# ReboostV2_MC.net
KiCad netlist of a schematic drawn in Altium Designer
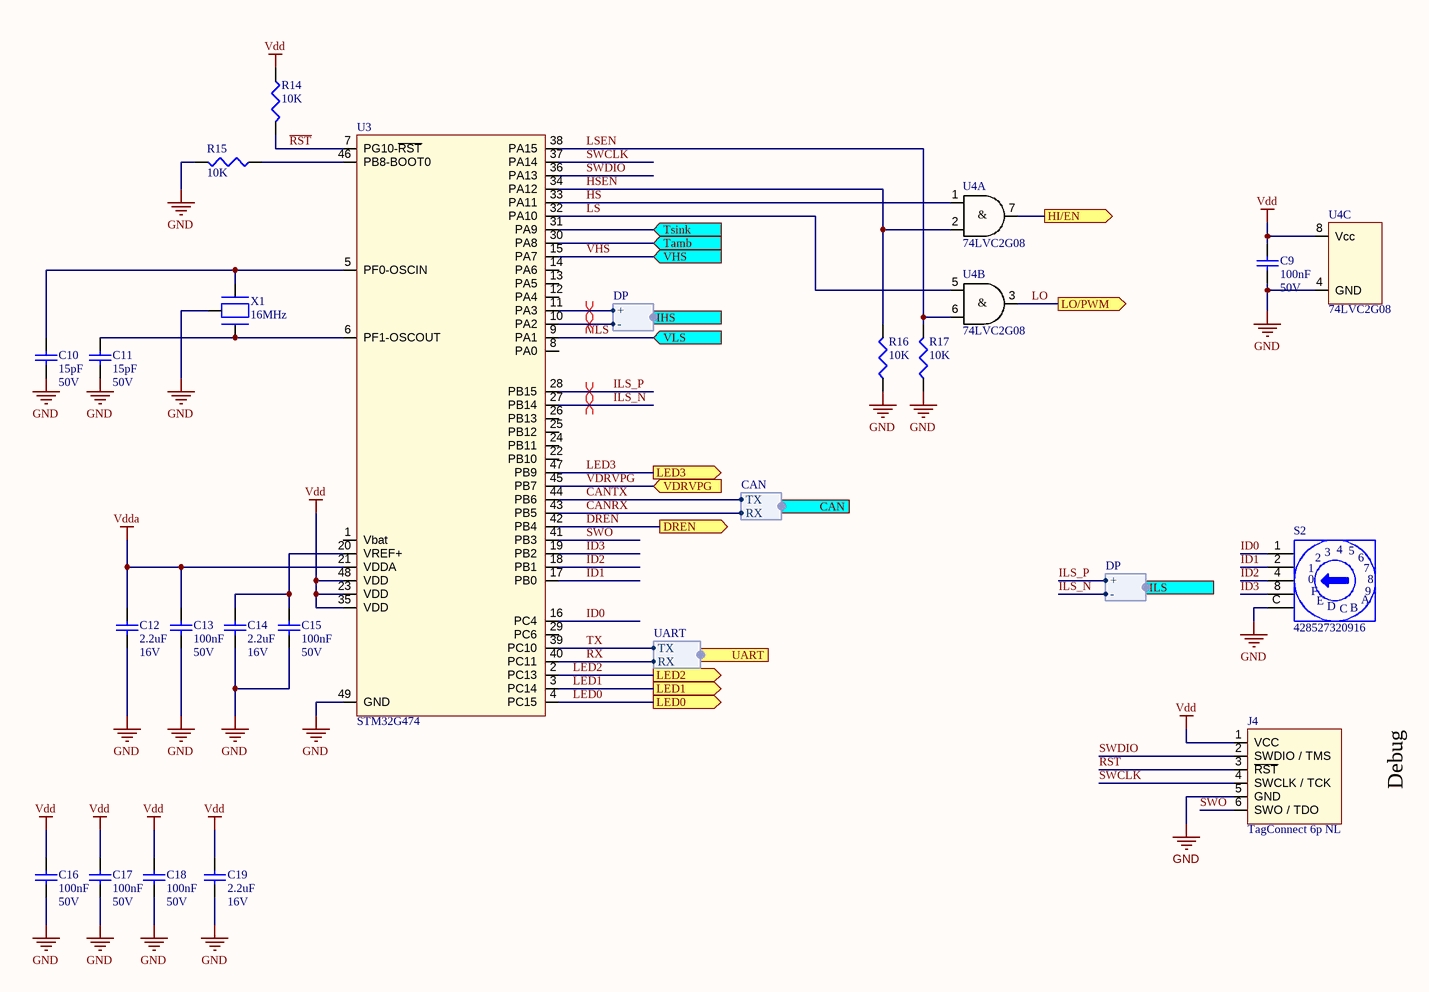
[diagram p0: ReboostV2_MC.SchDoc]

(export (version "E")
  (design (tool "Eeschema 10.0.6"))
  (components
    (comp (ref "C9")
      (value "100nF")
      (footprint "C0603")
      (description "Capacitor, 100nF, 50V, X7R")
      (fields
        (field (name "VOLTAGE RATING") "50V")
        (field (name "MANUFACTURER") "MULTICOMP")
        (field (name "MANUFACTURER PART NUMBER") "MCCA000255")
      )
      (libsource (lib "Reboostv2") (part "100nF/0603/CER/50V"))
    )
    (comp (ref "C10")
      (value "15pF")
      (footprint "C0603")
      (description "Capacitor, 15pF, 50V, C0G / NP0")
      (fields
        (field (name "VOLTAGE RATING") "50V")
        (field (name "MANUFACTURER") "MULTICOMP")
        (field (name "MANUFACTURER PART NUMBER") "MCCA000194")
      )
      (libsource (lib "Reboostv2") (part "15pF/0603/CER/50V"))
    )
    (comp (ref "C11")
      (value "15pF")
      (footprint "C0603")
      (description "Capacitor, 15pF, 50V, C0G / NP0")
      (fields
        (field (name "VOLTAGE RATING") "50V")
        (field (name "MANUFACTURER") "MULTICOMP")
        (field (name "MANUFACTURER PART NUMBER") "MCCA000194")
      )
      (libsource (lib "Reboostv2") (part "15pF/0603/CER/50V"))
    )
    (comp (ref "C12")
      (value "2.2uF")
      (footprint "C0603")
      (description "Capacitor, 2.2uF, 16V, X5R")
      (fields
        (field (name "VOLTAGE RATING") "16V")
        (field (name "MANUFACTURER") "MURATA")
        (field (name "MANUFACTURER PART NUMBER") "GRM188R61C225KE15D")
      )
      (libsource (lib "Reboostv2") (part "2.2uF/0603/CER/16V"))
    )
    (comp (ref "C13")
      (value "100nF")
      (footprint "C0603")
      (description "Capacitor, 100nF, 50V, X7R")
      (fields
        (field (name "VOLTAGE RATING") "50V")
        (field (name "MANUFACTURER") "MULTICOMP")
        (field (name "MANUFACTURER PART NUMBER") "MCCA000255")
      )
      (libsource (lib "Reboostv2") (part "100nF/0603/CER/50V"))
    )
    (comp (ref "C14")
      (value "2.2uF")
      (footprint "C0603")
      (description "Capacitor, 2.2uF, 16V, X5R")
      (fields
        (field (name "VOLTAGE RATING") "16V")
        (field (name "MANUFACTURER") "MURATA")
        (field (name "MANUFACTURER PART NUMBER") "GRM188R61C225KE15D")
      )
      (libsource (lib "Reboostv2") (part "2.2uF/0603/CER/16V"))
    )
    (comp (ref "C15")
      (value "100nF")
      (footprint "C0603")
      (description "Capacitor, 100nF, 50V, X7R")
      (fields
        (field (name "VOLTAGE RATING") "50V")
        (field (name "MANUFACTURER") "MULTICOMP")
        (field (name "MANUFACTURER PART NUMBER") "MCCA000255")
      )
      (libsource (lib "Reboostv2") (part "100nF/0603/CER/50V"))
    )
    (comp (ref "C16")
      (value "100nF")
      (footprint "C0603")
      (description "Capacitor, 100nF, 50V, X7R")
      (fields
        (field (name "VOLTAGE RATING") "50V")
        (field (name "MANUFACTURER") "MULTICOMP")
        (field (name "MANUFACTURER PART NUMBER") "MCCA000255")
      )
      (libsource (lib "Reboostv2") (part "100nF/0603/CER/50V"))
    )
    (comp (ref "C17")
      (value "100nF")
      (footprint "C0603")
      (description "Capacitor, 100nF, 50V, X7R")
      (fields
        (field (name "VOLTAGE RATING") "50V")
        (field (name "MANUFACTURER") "MULTICOMP")
        (field (name "MANUFACTURER PART NUMBER") "MCCA000255")
      )
      (libsource (lib "Reboostv2") (part "100nF/0603/CER/50V"))
    )
    (comp (ref "C18")
      (value "100nF")
      (footprint "C0603")
      (description "Capacitor, 100nF, 50V, X7R")
      (fields
        (field (name "VOLTAGE RATING") "50V")
        (field (name "MANUFACTURER") "MULTICOMP")
        (field (name "MANUFACTURER PART NUMBER") "MCCA000255")
      )
      (libsource (lib "Reboostv2") (part "100nF/0603/CER/50V"))
    )
    (comp (ref "C19")
      (value "2.2uF")
      (footprint "C0603")
      (description "Capacitor, 2.2uF, 16V, X5R")
      (fields
        (field (name "VOLTAGE RATING") "16V")
        (field (name "MANUFACTURER") "MURATA")
        (field (name "MANUFACTURER PART NUMBER") "GRM188R61C225KE15D")
      )
      (libsource (lib "Reboostv2") (part "2.2uF/0603/CER/16V"))
    )
    (comp (ref "J4")
      (value "TagConnect 6p NL")
      (footprint "TC2030-IDC-NL")
      (description "“No Legs” 6-pin Plug-of-Nails™ Cable fitted with a 6-pin 0.1″ pitch ribbon connector.")
      (fields
        (field (name "MANUFACTURER") "Tag-Connect LLC")
        (field (name "MANUFACTURER PART NUMBER") "TC2030-IDC-ND")
      )
      (libsource (lib "Reboostv2") (part "TC2030-IDC"))
    )
    (comp (ref "R14")
      (value "10K")
      (footprint "0603")
      (description "Resistor, 10K, 1%, 0.063W, 50V, 100PPM, 0603")
      (fields
        (field (name "MANUFACTURER") "VISHAY DRALORIC")
        (field (name "MANUFACTURER PART NUMBER") "CRCW060310K0FKEA")
      )
      (libsource (lib "Reboostv2") (part "10K/0603/0063W/50V"))
    )
    (comp (ref "R15")
      (value "10K")
      (footprint "0603")
      (description "Resistor, 10K, 1%, 0.063W, 50V, 100PPM, 0603")
      (fields
        (field (name "MANUFACTURER") "VISHAY DRALORIC")
        (field (name "MANUFACTURER PART NUMBER") "CRCW060310K0FKEA")
      )
      (libsource (lib "Reboostv2") (part "10K/0603/0063W/50V"))
    )
    (comp (ref "R16")
      (value "10K")
      (footprint "0603")
      (description "Resistor, 10K, 1%, 0.063W, 50V, 100PPM, 0603")
      (fields
        (field (name "MANUFACTURER") "VISHAY DRALORIC")
        (field (name "MANUFACTURER PART NUMBER") "CRCW060310K0FKEA")
      )
      (libsource (lib "Reboostv2") (part "10K/0603/0063W/50V"))
    )
    (comp (ref "R17")
      (value "10K")
      (footprint "0603")
      (description "Resistor, 10K, 1%, 0.063W, 50V, 100PPM, 0603")
      (fields
        (field (name "MANUFACTURER") "VISHAY DRALORIC")
        (field (name "MANUFACTURER PART NUMBER") "CRCW060310K0FKEA")
      )
      (libsource (lib "Reboostv2") (part "10K/0603/0063W/50V"))
    )
    (comp (ref "S2")
      (value "428527320916")
      (footprint "42852732091x_16p")
      (description "WS-ROTV THT Rotary Switch with Arrow Type Actuator, 10x10mm, 16 positions")
      (fields (field (name "MANUFACTURER") "Wurth Elektronik") (field (name "PUBLISHER") "Wurth Elektronik"))
      (libsource (lib "Reboostv2") (part "428527320916"))
    )
    (comp (ref "U3")
      (value "STM32G474")
      (footprint "QFN48")
      (description "ARM MCU, STM32 Family STM32G4 Series Microcontrollers, ARM Cortex-M4F, 32bit, 170 MHz, 512 KB")
      (fields (field (name "MANUFACTURER") "STMicroelectronics") (field (name "MPN") "STM32G474CEU6"))
      (libsource (lib "Reboostv2") (part "STM32G474CEU6"))
    )
    (comp (ref "U4")
      (value "74LVC2G08")
      (footprint "TSSOP8")
      (description "Dual 2-input AND gate")
      (fields
        (field (name "MANUFACTURER") "Nexperia")
        (field (name "MANUFACTURER PART NUMBER") "74LVC2G08DP,125")
      )
      (libsource (lib "Reboostv2") (part "74LVC2G08"))
    )
    (comp (ref "X1")
      (value "16MHz")
      (footprint "7M")
      (description "CRYSTAL, 16MHz,18PF CL, 3.2X2.5MM SMT")
      (fields (field (name "MANUFACTURER") "TXC") (field (name "MANUFACTURER PART NUMBER") "7M-16.000MAAJ-T"))
      (libsource (lib "Reboostv2") (part "7M-16.000MAAJ-T"))
    )
  )
  (nets
    (net (code "4") (name "/CANRX") (class "Default")
      (node (ref "U3") (pin "43") (pinfunction "PB5_43") (pintype "passive"))
    )
    (net (code "5") (name "/CANTX") (class "Default")
      (node (ref "U3") (pin "44") (pinfunction "PB6_44") (pintype "passive"))
    )
    (net (code "6") (name "/DREN") (class "Default")
      (node (ref "U3") (pin "42") (pinfunction "PB4_42") (pintype "passive"))
    )
    (net (code "7") (name "/HI{slash}EN") (class "Default")
      (node (ref "U4") (pin "7") (pinfunction "Y_7") (pintype "passive"))
    )
    (net (code "8") (name "/HS") (class "Default")
      (node (ref "U3") (pin "33") (pinfunction "PA11_33") (pintype "passive"))
      (node (ref "U4") (pin "1") (pinfunction "A_1") (pintype "passive"))
    )
    (net (code "9") (name "/HSEN") (class "Default")
      (node (ref "R16") (pin "2") (pinfunction "2_2") (pintype "passive"))
      (node (ref "U3") (pin "34") (pinfunction "PA12_34") (pintype "passive"))
      (node (ref "U4") (pin "2") (pinfunction "B_2") (pintype "passive"))
    )
    (net (code "10") (name "/ID0") (class "Default")
      (node (ref "S2") (pin "1") (pinfunction "1_1") (pintype "passive"))
      (node (ref "U3") (pin "16") (pinfunction "PC4_16") (pintype "passive"))
    )
    (net (code "11") (name "/ID1") (class "Default")
      (node (ref "S2") (pin "2") (pinfunction "2_2") (pintype "passive"))
      (node (ref "U3") (pin "17") (pinfunction "PB0_17") (pintype "passive"))
    )
    (net (code "12") (name "/ID2") (class "Default")
      (node (ref "S2") (pin "4") (pinfunction "4_4") (pintype "passive"))
      (node (ref "U3") (pin "18") (pinfunction "PB1_18") (pintype "passive"))
    )
    (net (code "13") (name "/ID3") (class "Default")
      (node (ref "S2") (pin "8") (pinfunction "8_8") (pintype "passive"))
      (node (ref "U3") (pin "19") (pinfunction "PB2_19") (pintype "passive"))
    )
    (net (code "14") (name "/ILS_N") (class "Default")
      (node (ref "U3") (pin "27") (pinfunction "PB14_27") (pintype "passive"))
    )
    (net (code "15") (name "/ILS_P") (class "Default")
      (node (ref "U3") (pin "28") (pinfunction "PB15_28") (pintype "passive"))
    )
    (net (code "16") (name "/LED0") (class "Default")
      (node (ref "U3") (pin "4") (pinfunction "PC15_4") (pintype "passive"))
    )
    (net (code "17") (name "/LED1") (class "Default")
      (node (ref "U3") (pin "3") (pinfunction "PC14_3") (pintype "passive"))
    )
    (net (code "18") (name "/LED2") (class "Default")
      (node (ref "U3") (pin "2") (pinfunction "PC13_2") (pintype "passive"))
    )
    (net (code "19") (name "/LED3") (class "Default")
      (node (ref "U3") (pin "47") (pinfunction "PB9_47") (pintype "passive"))
    )
    (net (code "20") (name "/LO") (class "Default")
      (node (ref "U4") (pin "3") (pinfunction "Y_3") (pintype "passive"))
    )
    (net (code "21") (name "/LS") (class "Default")
      (node (ref "U3") (pin "32") (pinfunction "PA10_32") (pintype "passive"))
      (node (ref "U4") (pin "5") (pinfunction "A_5") (pintype "passive"))
    )
    (net (code "22") (name "/LSEN") (class "Default")
      (node (ref "R17") (pin "2") (pinfunction "2_2") (pintype "passive"))
      (node (ref "U3") (pin "38") (pinfunction "PA15_38") (pintype "passive"))
      (node (ref "U4") (pin "6") (pinfunction "B_6") (pintype "passive"))
    )
    (net (code "23") (name "/RX") (class "Default")
      (node (ref "U3") (pin "40") (pinfunction "PC11_40") (pintype "passive"))
    )
    (net (code "24") (name "/SWCLK") (class "Default")
      (node (ref "J4") (pin "4") (pinfunction "SWCLK_/_TCK_4") (pintype "passive"))
      (node (ref "U3") (pin "37") (pinfunction "PA14_37") (pintype "passive"))
    )
    (net (code "25") (name "/SWDIO") (class "Default")
      (node (ref "J4") (pin "2") (pinfunction "SWDIO_/_TMS_2") (pintype "passive"))
      (node (ref "U3") (pin "36") (pinfunction "PA13_36") (pintype "passive"))
    )
    (net (code "26") (name "/SWO") (class "Default")
      (node (ref "J4") (pin "6") (pinfunction "SWO_/_TDO_6") (pintype "passive"))
      (node (ref "U3") (pin "41") (pinfunction "PB3_41") (pintype "passive"))
    )
    (net (code "27") (name "/TX") (class "Default")
      (node (ref "U3") (pin "39") (pinfunction "PC10_39") (pintype "passive"))
    )
    (net (code "28") (name "/Tamb") (class "Default")
      (node (ref "U3") (pin "30") (pinfunction "PA8_30") (pintype "passive"))
    )
    (net (code "29") (name "/Tsink") (class "Default")
      (node (ref "U3") (pin "31") (pinfunction "PA9_31") (pintype "passive"))
    )
    (net (code "30") (name "/VDRVPG") (class "Default")
      (node (ref "U3") (pin "45") (pinfunction "PB7_45") (pintype "passive"))
    )
    (net (code "31") (name "/VHS") (class "Default")
      (node (ref "U3") (pin "15") (pinfunction "PA7_15") (pintype "passive"))
    )
    (net (code "32") (name "/VLS") (class "Default")
      (node (ref "U3") (pin "9") (pinfunction "PA1_9") (pintype "passive"))
    )
    (net (code "36") (name "/~{RST}") (class "Default")
      (node (ref "J4") (pin "3") (pinfunction "~{RST}_3") (pintype "passive"))
      (node (ref "R14") (pin "2") (pinfunction "2_2") (pintype "passive"))
      (node (ref "U3") (pin "7") (pinfunction "PG10-~{RST}_7") (pintype "passive"))
    )
    (net (code "37") (name "GND") (class "Default")
      (node (ref "C10") (pin "1") (pinfunction "1_1") (pintype "passive"))
      (node (ref "C11") (pin "1") (pinfunction "1_1") (pintype "passive"))
      (node (ref "C12") (pin "1") (pinfunction "1_1") (pintype "passive"))
      (node (ref "C13") (pin "1") (pinfunction "1_1") (pintype "passive"))
      (node (ref "C14") (pin "1") (pinfunction "1_1") (pintype "passive"))
      (node (ref "C15") (pin "1") (pinfunction "1_1") (pintype "passive"))
      (node (ref "C16") (pin "1") (pinfunction "1_1") (pintype "passive"))
      (node (ref "C17") (pin "1") (pinfunction "1_1") (pintype "passive"))
      (node (ref "C18") (pin "1") (pinfunction "1_1") (pintype "passive"))
      (node (ref "C19") (pin "1") (pinfunction "1_1") (pintype "passive"))
      (node (ref "C9") (pin "1") (pinfunction "1_1") (pintype "passive"))
      (node (ref "J4") (pin "5") (pinfunction "GND_5") (pintype "passive"))
      (node (ref "R15") (pin "2") (pinfunction "2_2") (pintype "passive"))
      (node (ref "R16") (pin "1") (pinfunction "1_1") (pintype "passive"))
      (node (ref "R17") (pin "1") (pinfunction "1_1") (pintype "passive"))
      (node (ref "S2") (pin "C") (pinfunction "C_C") (pintype "passive"))
      (node (ref "U3") (pin "49") (pinfunction "GND_49") (pintype "passive"))
      (node (ref "U4") (pin "4") (pinfunction "GND_4") (pintype "passive"))
      (node (ref "X1") (pin "0") (pinfunction "0_0") (pintype "power_in"))
    )
    (net (code "38") (name "Net-(U3-PB8-BOOT0)") (class "Default")
      (node (ref "R15") (pin "1") (pinfunction "1_1") (pintype "passive"))
      (node (ref "U3") (pin "46") (pinfunction "PB8-BOOT0_46") (pintype "passive"))
    )
    (net (code "39") (name "Net-(U3-PF0-OSCIN)") (class "Default")
      (node (ref "C10") (pin "2") (pinfunction "2_2") (pintype "passive"))
      (node (ref "U3") (pin "5") (pinfunction "PF0-OSCIN_5") (pintype "passive"))
      (node (ref "X1") (pin "1") (pinfunction "1_1") (pintype "passive"))
    )
    (net (code "40") (name "Net-(U3-PF1-OSCOUT)") (class "Default")
      (node (ref "C11") (pin "2") (pinfunction "2_2") (pintype "passive"))
      (node (ref "U3") (pin "6") (pinfunction "PF1-OSCOUT_6") (pintype "passive"))
      (node (ref "X1") (pin "2") (pinfunction "2_2") (pintype "passive"))
    )
    (net (code "41") (name "Net-(U3-VREF+)") (class "Default")
      (node (ref "C14") (pin "2") (pinfunction "2_2") (pintype "passive"))
      (node (ref "C15") (pin "2") (pinfunction "2_2") (pintype "passive"))
      (node (ref "U3") (pin "20") (pinfunction "VREF+_20") (pintype "passive"))
    )
    (net (code "42") (name "Vdd") (class "Default")
      (node (ref "C16") (pin "2") (pinfunction "2_2") (pintype "passive"))
      (node (ref "C17") (pin "2") (pinfunction "2_2") (pintype "passive"))
      (node (ref "C18") (pin "2") (pinfunction "2_2") (pintype "passive"))
      (node (ref "C19") (pin "2") (pinfunction "2_2") (pintype "passive"))
      (node (ref "C9") (pin "2") (pinfunction "2_2") (pintype "passive"))
      (node (ref "J4") (pin "1") (pinfunction "VCC_1") (pintype "passive"))
      (node (ref "R14") (pin "1") (pinfunction "1_1") (pintype "passive"))
      (node (ref "U3") (pin "23") (pinfunction "VDD_23") (pintype "passive"))
      (node (ref "U3") (pin "35") (pinfunction "VDD_35") (pintype "passive"))
      (node (ref "U3") (pin "48") (pinfunction "VDD_48") (pintype "passive"))
      (node (ref "U4") (pin "8") (pinfunction "Vcc_8") (pintype "passive"))
    )
    (net (code "43") (name "Vdda") (class "Default")
      (node (ref "C12") (pin "2") (pinfunction "2_2") (pintype "passive"))
      (node (ref "C13") (pin "2") (pinfunction "2_2") (pintype "passive"))
      (node (ref "U3") (pin "21") (pinfunction "VDDA_21") (pintype "passive"))
    )
    (net (code "44") (name "unconnected-(U3-PA0-Pad8)") (class "Default")
      (node (ref "U3") (pin "8") (pinfunction "PA0_8") (pintype "passive"))
    )
    (net (code "45") (name "unconnected-(U3-PA2-Pad10)") (class "Default")
      (node (ref "U3") (pin "10") (pinfunction "PA2_10") (pintype "passive"))
    )
    (net (code "46") (name "unconnected-(U3-PA3-Pad11)") (class "Default")
      (node (ref "U3") (pin "11") (pinfunction "PA3_11") (pintype "passive"))
    )
    (net (code "47") (name "unconnected-(U3-PA4-Pad12)") (class "Default")
      (node (ref "U3") (pin "12") (pinfunction "PA4_12") (pintype "passive"))
    )
    (net (code "48") (name "unconnected-(U3-PA5-Pad13)") (class "Default")
      (node (ref "U3") (pin "13") (pinfunction "PA5_13") (pintype "passive"))
    )
    (net (code "49") (name "unconnected-(U3-PA6-Pad14)") (class "Default")
      (node (ref "U3") (pin "14") (pinfunction "PA6_14") (pintype "passive"))
    )
    (net (code "50") (name "unconnected-(U3-PB10-Pad22)") (class "Default")
      (node (ref "U3") (pin "22") (pinfunction "PB10_22") (pintype "passive"))
    )
    (net (code "51") (name "unconnected-(U3-PB11-Pad24)") (class "Default")
      (node (ref "U3") (pin "24") (pinfunction "PB11_24") (pintype "passive"))
    )
    (net (code "52") (name "unconnected-(U3-PB12-Pad25)") (class "Default")
      (node (ref "U3") (pin "25") (pinfunction "PB12_25") (pintype "passive"))
    )
    (net (code "53") (name "unconnected-(U3-PB13-Pad26)") (class "Default")
      (node (ref "U3") (pin "26") (pinfunction "PB13_26") (pintype "passive"))
    )
    (net (code "54") (name "unconnected-(U3-PC6-Pad29)") (class "Default")
      (node (ref "U3") (pin "29") (pinfunction "PC6_29") (pintype "passive"))
    )
    (net (code "55") (name "unconnected-(U3-Vbat-Pad1)") (class "Default")
      (node (ref "U3") (pin "1") (pinfunction "Vbat_1") (pintype "passive"))
    )
  )
)
